# MultiRotor_0_1.net
KiCad netlist of a schematic drawn in Altium Designer
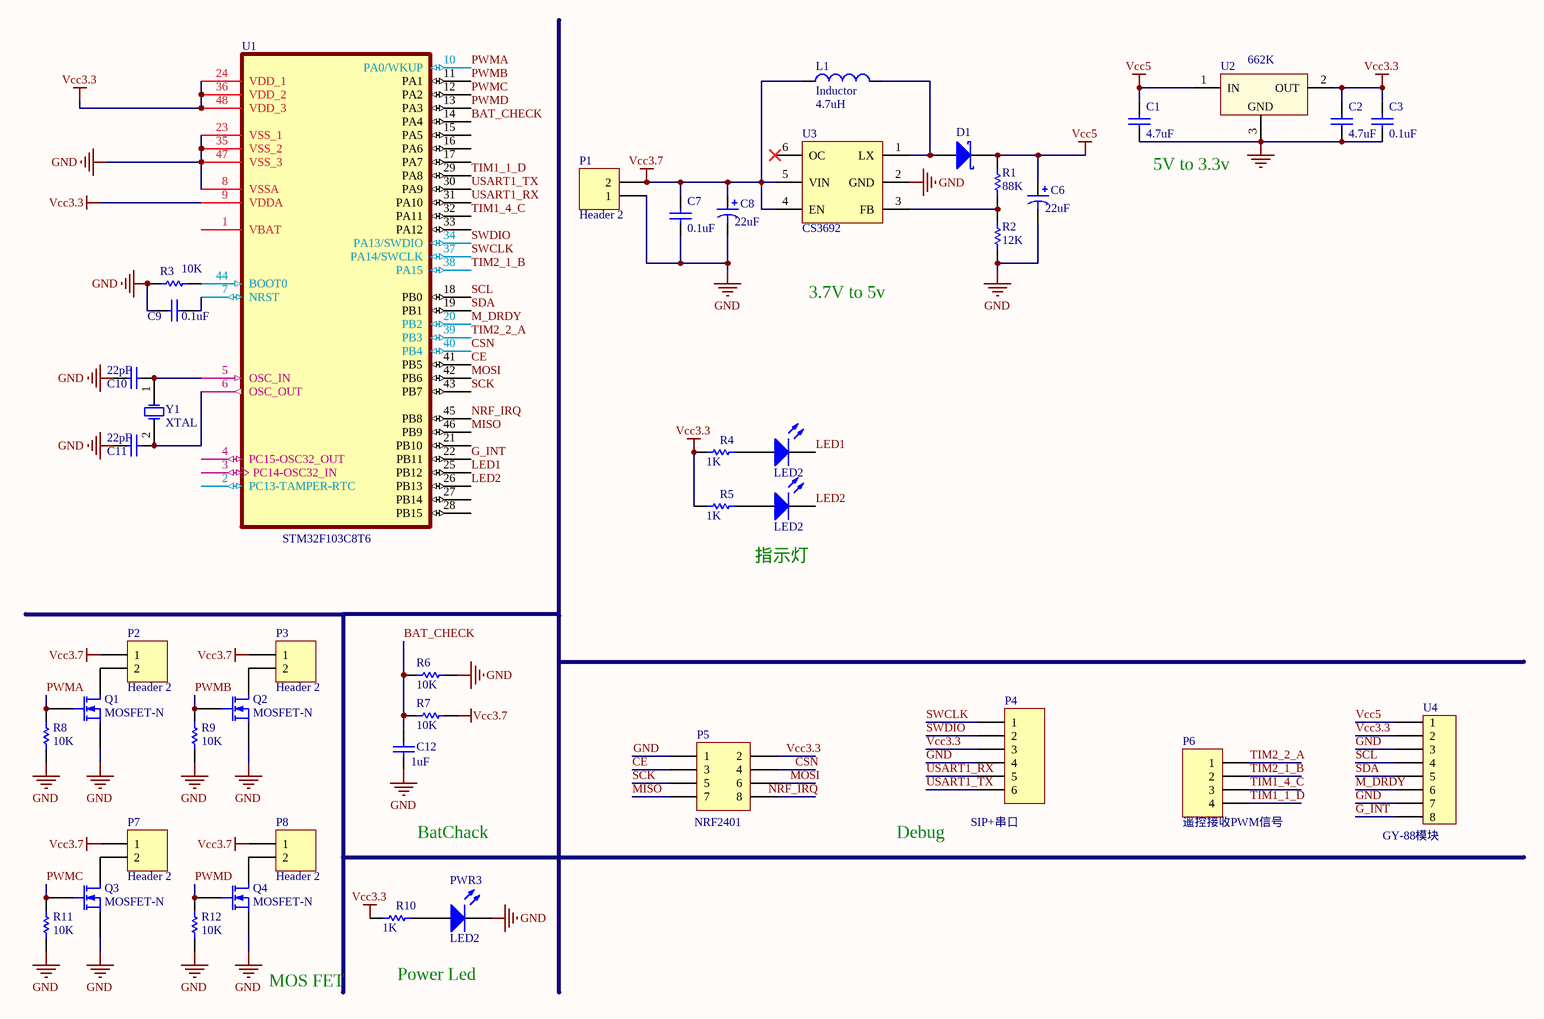
[diagram p0: MultiRotor_0.1.SchDoc]

(export (version "E")
  (design (tool "Eeschema 10.0.6"))
  (components
    (comp (ref "C1")
      (value "4.7uF")
      (footprint "CAP[1206]")
      (description "Capacitor")
      (fields (field (name "Comment") "Cap Pol1") (field (name "PUBLISHER") "Altium Limited"))
      (libsource (lib "Miscellaneous Devices") (part "Cap"))
    )
    (comp (ref "C2")
      (value "4.7uF")
      (footprint "CAP[1206]")
      (description "Capacitor")
      (fields (field (name "Comment") "Cap Pol1") (field (name "PUBLISHER") "Altium Limited"))
      (libsource (lib "Miscellaneous Devices") (part "Cap"))
    )
    (comp (ref "C3")
      (value "0.1uF")
      (footprint "CAP[0805]")
      (description "Capacitor")
      (fields (field (name "Comment") "Cap") (field (name "PUBLISHER") "Altium Limited"))
      (libsource (lib "Miscellaneous Devices") (part "Cap"))
    )
    (comp (ref "C6")
      (value "22uF")
      (footprint "CAP[1206]")
      (description "Polarized Capacitor (Radial)")
      (fields (field (name "Comment") "Cap") (field (name "PUBLISHER") "Altium Limited"))
      (libsource (lib "Miscellaneous Devices") (part "Cap Pol1"))
    )
    (comp (ref "C7")
      (value "0.1uF")
      (footprint "CAP[0805]")
      (description "Capacitor")
      (fields (field (name "Comment") "Cap") (field (name "PUBLISHER") "Altium Limited"))
      (libsource (lib "Miscellaneous Devices") (part "Cap"))
    )
    (comp (ref "C8")
      (value "22uF")
      (footprint "CAP[1206]")
      (description "Polarized Capacitor (Radial)")
      (fields (field (name "Comment") "Cap") (field (name "PUBLISHER") "Altium Limited"))
      (libsource (lib "Miscellaneous Devices") (part "Cap Pol1"))
    )
    (comp (ref "C9")
      (value "0.1uF")
      (footprint "CAP[0805]")
      (description "Capacitor")
      (fields (field (name "Comment") "Cap") (field (name "PUBLISHER") "Altium Limited"))
      (libsource (lib "Miscellaneous Devices") (part "Cap"))
    )
    (comp (ref "C10")
      (value "22pF")
      (footprint "CAP[0805]")
      (description "Capacitor")
      (fields (field (name "Comment") "Cap") (field (name "PUBLISHER") "Altium Limited"))
      (libsource (lib "Miscellaneous Devices") (part "Cap"))
    )
    (comp (ref "C11")
      (value "22pF")
      (footprint "CAP[0805]")
      (description "Capacitor")
      (fields (field (name "Comment") "Cap") (field (name "PUBLISHER") "Altium Limited"))
      (libsource (lib "Miscellaneous Devices") (part "Cap"))
    )
    (comp (ref "C12")
      (value "1uF")
      (footprint "CAP[0805]")
      (description "Capacitor")
      (fields (field (name "Comment") "Cap") (field (name "PUBLISHER") "Altium Limited"))
      (libsource (lib "Miscellaneous Devices") (part "Cap"))
    )
    (comp (ref "D1")
      (value "1n5819")
      (footprint "DO-214AC - Diode")
      (description "Diode_P6KE")
      (libsource (lib "BY") (part "Diode_P6KE"))
    )
    (comp (ref "L1")
      (value "Inductor")
      (footprint "Inductor_T10uH")
      (fields (field (name "ALTIUM_UNNAMED_1") "4.7uH"))
      (libsource (lib "BY") (part "Inductor"))
    )
    (comp (ref "P1")
      (value "Header 2")
      (footprint "H2.54-1X2")
      (description "Header, 2-Pin")
      (fields (field (name "PUBLISHER") "Altium Limited"))
      (libsource (lib "") (part "Header 2_1"))
    )
    (comp (ref "P2")
      (value "Header 2")
      (footprint "H2.54-1X2")
      (description "Header, 2-Pin")
      (fields (field (name "PUBLISHER") "Altium Limited"))
      (libsource (lib "Miscellaneous Connectors") (part "Header 2"))
    )
    (comp (ref "P3")
      (value "Header 2")
      (footprint "H2.54-1X2")
      (description "Header, 2-Pin")
      (fields (field (name "PUBLISHER") "Altium Limited"))
      (libsource (lib "Miscellaneous Connectors") (part "Header 2"))
    )
    (comp (ref "P4")
      (value "SIP+串口")
      (footprint "HDR1X6")
      (description "Header, 6-Pin")
      (fields (field (name "PUBLISHER") "Altium Limited"))
      (libsource (lib "Miscellaneous Connectors") (part "Header 6"))
    )
    (comp (ref "P5")
      (value "NRF2401")
      (footprint "NRF(2401)模块")
      (description "Header, 4-Pin, Dual row")
      (fields (field (name "PUBLISHER") "Altium Limited"))
      (libsource (lib "Miscellaneous Connectors") (part "Header 4X2"))
    )
    (comp (ref "P6")
      (value "遥控接收PWM信号")
      (footprint "H2.54-1X4")
      (description "Header, 4-Pin")
      (fields (field (name "PUBLISHER") "Altium Limited"))
      (libsource (lib "Miscellaneous Connectors") (part "Header 4"))
    )
    (comp (ref "P7")
      (value "Header 2")
      (footprint "H2.54-1X2")
      (description "Header, 2-Pin")
      (fields (field (name "PUBLISHER") "Altium Limited"))
      (libsource (lib "Miscellaneous Connectors") (part "Header 2"))
    )
    (comp (ref "P8")
      (value "Header 2")
      (footprint "H2.54-1X2")
      (description "Header, 2-Pin")
      (fields (field (name "PUBLISHER") "Altium Limited"))
      (libsource (lib "Miscellaneous Connectors") (part "Header 2"))
    )
    (comp (ref "PWR1")
      (value "LED2")
      (footprint "3.2X1.6X1.1")
      (description "Typical RED, GREEN, YELLOW, AMBER GaAs LED")
      (fields (field (name "PUBLISHER") "Altium Limited"))
      (libsource (lib "Miscellaneous Devices") (part "LED2"))
    )
    (comp (ref "PWR2")
      (value "LED2")
      (footprint "3.2X1.6X1.1")
      (description "Typical RED, GREEN, YELLOW, AMBER GaAs LED")
      (fields (field (name "PUBLISHER") "Altium Limited"))
      (libsource (lib "Miscellaneous Devices") (part "LED2"))
    )
    (comp (ref "PWR3")
      (value "LED2")
      (footprint "3.2X1.6X1.1")
      (description "Typical RED, GREEN, YELLOW, AMBER GaAs LED")
      (fields (field (name "PUBLISHER") "Altium Limited"))
      (libsource (lib "Miscellaneous Devices") (part "LED2"))
    )
    (comp (ref "Q1")
      (value "MOSFET-N")
      (footprint "SOT23")
      (description "N-Channel MOSFET")
      (fields (field (name "PUBLISHER") "Altium Limited"))
      (libsource (lib "Miscellaneous Devices") (part "MOSFET-N"))
    )
    (comp (ref "Q2")
      (value "MOSFET-N")
      (footprint "SOT23")
      (description "N-Channel MOSFET")
      (fields (field (name "PUBLISHER") "Altium Limited"))
      (libsource (lib "Miscellaneous Devices") (part "MOSFET-N"))
    )
    (comp (ref "Q3")
      (value "MOSFET-N")
      (footprint "SOT23")
      (description "N-Channel MOSFET")
      (fields (field (name "PUBLISHER") "Altium Limited"))
      (libsource (lib "Miscellaneous Devices") (part "MOSFET-N"))
    )
    (comp (ref "Q4")
      (value "MOSFET-N")
      (footprint "SOT23")
      (description "N-Channel MOSFET")
      (fields (field (name "PUBLISHER") "Altium Limited"))
      (libsource (lib "Miscellaneous Devices") (part "MOSFET-N"))
    )
    (comp (ref "R1")
      (value "88K")
      (footprint "RES[0805]")
      (description "Resistor")
      (fields (field (name "Comment") "Res1") (field (name "PUBLISHER") "Altium Limited"))
      (libsource (lib "Miscellaneous Devices") (part "Res1"))
    )
    (comp (ref "R2")
      (value "12K")
      (footprint "RES[0805]")
      (description "Resistor")
      (fields (field (name "Comment") "Res1") (field (name "PUBLISHER") "Altium Limited"))
      (libsource (lib "Miscellaneous Devices") (part "Res1"))
    )
    (comp (ref "R3")
      (value "10K")
      (footprint "RES[0805]")
      (description "Resistor")
      (fields (field (name "Comment") "Res1") (field (name "PUBLISHER") "Altium Limited"))
      (libsource (lib "Miscellaneous Devices") (part "Res1"))
    )
    (comp (ref "R4")
      (value "1K")
      (footprint "RES[0805]")
      (description "Resistor")
      (fields (field (name "Comment") "Res1") (field (name "PUBLISHER") "Altium Limited"))
      (libsource (lib "Miscellaneous Devices") (part "Res1"))
    )
    (comp (ref "R5")
      (value "1K")
      (footprint "RES[0805]")
      (description "Resistor")
      (fields (field (name "Comment") "Res1") (field (name "PUBLISHER") "Altium Limited"))
      (libsource (lib "Miscellaneous Devices") (part "Res1"))
    )
    (comp (ref "R6")
      (value "10K")
      (footprint "RES[0805]")
      (description "Resistor")
      (fields (field (name "Comment") "Res1") (field (name "PUBLISHER") "Altium Limited"))
      (libsource (lib "Miscellaneous Devices") (part "Res1"))
    )
    (comp (ref "R7")
      (value "10K")
      (footprint "RES[0805]")
      (description "Resistor")
      (fields (field (name "Comment") "Res1") (field (name "PUBLISHER") "Altium Limited"))
      (libsource (lib "Miscellaneous Devices") (part "Res1"))
    )
    (comp (ref "R8")
      (value "10K")
      (footprint "RES[0805]")
      (description "Resistor")
      (fields (field (name "Comment") "Res1") (field (name "PUBLISHER") "Altium Limited"))
      (libsource (lib "Miscellaneous Devices") (part "Res1"))
    )
    (comp (ref "R9")
      (value "10K")
      (footprint "RES[0805]")
      (description "Resistor")
      (fields (field (name "Comment") "Res1") (field (name "PUBLISHER") "Altium Limited"))
      (libsource (lib "Miscellaneous Devices") (part "Res1"))
    )
    (comp (ref "R10")
      (value "1K")
      (footprint "RES[0805]")
      (description "Resistor")
      (fields (field (name "Comment") "Res1") (field (name "PUBLISHER") "Altium Limited"))
      (libsource (lib "Miscellaneous Devices") (part "Res1"))
    )
    (comp (ref "R11")
      (value "10K")
      (footprint "RES[0805]")
      (description "Resistor")
      (fields (field (name "Comment") "Res1") (field (name "PUBLISHER") "Altium Limited"))
      (libsource (lib "Miscellaneous Devices") (part "Res1"))
    )
    (comp (ref "R12")
      (value "10K")
      (footprint "RES[0805]")
      (description "Resistor")
      (fields (field (name "Comment") "Res1") (field (name "PUBLISHER") "Altium Limited"))
      (libsource (lib "Miscellaneous Devices") (part "Res1"))
    )
    (comp (ref "U1")
      (value "STM32F103C8T6")
      (footprint "LQFP-48")
      (description "STM32 ARM-based 32-bit MCU with 64 Kbytes Flash, 48-pin LQFP, Industrial Temperature")
      (fields (field (name "PUBLISHER") "*"))
      (libsource (lib "STM32F103C8T6") (part "STM32F103C8T6"))
    )
    (comp (ref "U2") (value "662K") (footprint "SOT23") (libsource (lib "WB") (part "AMS1117-3.3")))
    (comp (ref "U3")
      (value "CS3692")
      (footprint "SOT23-6")
      (description "Generic Phase Locked Loop")
      (fields (field (name "PUBLISHER") "Altium Limited"))
      (libsource (lib "MultiRotor") (part "CS3692"))
    )
    (comp (ref "U4") (value "GY-88模块") (footprint "MPU-6050") (libsource (lib "FAST") (part "MPU-6050模块")))
    (comp (ref "Y1")
      (value "XTAL")
      (footprint "XTAL")
      (description "Crystal Oscillator")
      (fields (field (name "PUBLISHER") "Altium Limited"))
      (libsource (lib "Miscellaneous Devices") (part "XTAL"))
    )
  )
  (nets
    (net (code "1") (name "/BAT_CHECK") (class "Default")
      (node (ref "C12") (pin "2") (pinfunction "2_2") (pintype "passive"))
      (node (ref "R6") (pin "2") (pinfunction "2_2") (pintype "passive"))
      (node (ref "R7") (pin "2") (pinfunction "2_2") (pintype "passive"))
      (node (ref "U1") (pin "14") (pinfunction "PA4_14") (pintype "bidirectional"))
    )
    (net (code "2") (name "/CE") (class "Default")
      (node (ref "P5") (pin "3") (pinfunction "3_3") (pintype "passive"))
      (node (ref "U1") (pin "41") (pinfunction "PB5_41") (pintype "bidirectional"))
    )
    (net (code "3") (name "/CSN") (class "Default")
      (node (ref "P5") (pin "4") (pinfunction "4_4") (pintype "passive"))
      (node (ref "U1") (pin "40") (pinfunction "PB4_40") (pintype "bidirectional"))
    )
    (net (code "4") (name "/G_INT") (class "Default")
      (node (ref "U1") (pin "22") (pinfunction "PB11_22") (pintype "bidirectional"))
      (node (ref "U4") (pin "8") (pinfunction "8_8") (pintype "passive"))
    )
    (net (code "5") (name "/LED1") (class "Default")
      (node (ref "PWR1") (pin "2") (pinfunction "K_2") (pintype "passive"))
      (node (ref "U1") (pin "25") (pinfunction "PB12_25") (pintype "bidirectional"))
    )
    (net (code "6") (name "/LED2") (class "Default")
      (node (ref "PWR2") (pin "2") (pinfunction "K_2") (pintype "passive"))
      (node (ref "U1") (pin "26") (pinfunction "PB13_26") (pintype "bidirectional"))
    )
    (net (code "7") (name "/MISO") (class "Default")
      (node (ref "P5") (pin "7") (pinfunction "7_7") (pintype "passive"))
      (node (ref "U1") (pin "46") (pinfunction "PB9_46") (pintype "bidirectional"))
    )
    (net (code "8") (name "/MOSI") (class "Default")
      (node (ref "P5") (pin "6") (pinfunction "6_6") (pintype "passive"))
      (node (ref "U1") (pin "42") (pinfunction "PB6_42") (pintype "bidirectional"))
    )
    (net (code "9") (name "/M_DRDY") (class "Default")
      (node (ref "U1") (pin "20") (pinfunction "PB2_20") (pintype "bidirectional"))
      (node (ref "U4") (pin "6") (pinfunction "6_6") (pintype "passive"))
    )
    (net (code "10") (name "/NRF_IRQ") (class "Default")
      (node (ref "U1") (pin "45") (pinfunction "PB8_45") (pintype "bidirectional"))
    )
    (net (code "11") (name "/PWMA") (class "Default")
      (node (ref "Q1") (pin "2") (pinfunction "G_2") (pintype "passive"))
      (node (ref "R8") (pin "2") (pinfunction "2_2") (pintype "passive"))
      (node (ref "U1") (pin "10") (pinfunction "PA0/WKUP_10") (pintype "bidirectional"))
    )
    (net (code "12") (name "/PWMB") (class "Default")
      (node (ref "Q2") (pin "2") (pinfunction "G_2") (pintype "passive"))
      (node (ref "R9") (pin "2") (pinfunction "2_2") (pintype "passive"))
      (node (ref "U1") (pin "11") (pinfunction "PA1_11") (pintype "bidirectional"))
    )
    (net (code "13") (name "/PWMC") (class "Default")
      (node (ref "Q3") (pin "2") (pinfunction "G_2") (pintype "passive"))
      (node (ref "R11") (pin "2") (pinfunction "2_2") (pintype "passive"))
      (node (ref "U1") (pin "12") (pinfunction "PA2_12") (pintype "bidirectional"))
    )
    (net (code "14") (name "/PWMD") (class "Default")
      (node (ref "Q4") (pin "2") (pinfunction "G_2") (pintype "passive"))
      (node (ref "R12") (pin "2") (pinfunction "2_2") (pintype "passive"))
      (node (ref "U1") (pin "13") (pinfunction "PA3_13") (pintype "bidirectional"))
    )
    (net (code "15") (name "/SCK") (class "Default")
      (node (ref "P5") (pin "5") (pinfunction "5_5") (pintype "passive"))
      (node (ref "U1") (pin "43") (pinfunction "PB7_43") (pintype "bidirectional"))
    )
    (net (code "16") (name "/SCL") (class "Default")
      (node (ref "U1") (pin "18") (pinfunction "PB0_18") (pintype "bidirectional"))
      (node (ref "U4") (pin "4") (pinfunction "4_4") (pintype "passive"))
    )
    (net (code "17") (name "/SDA") (class "Default")
      (node (ref "U1") (pin "19") (pinfunction "PB1_19") (pintype "bidirectional"))
      (node (ref "U4") (pin "5") (pinfunction "5_5") (pintype "passive"))
    )
    (net (code "18") (name "/SWCLK") (class "Default")
      (node (ref "P4") (pin "1") (pinfunction "1_1") (pintype "passive"))
      (node (ref "U1") (pin "37") (pinfunction "PA14/SWCLK_37") (pintype "bidirectional"))
    )
    (net (code "19") (name "/SWDIO") (class "Default")
      (node (ref "P4") (pin "2") (pinfunction "2_2") (pintype "passive"))
      (node (ref "U1") (pin "34") (pinfunction "PA13/SWDIO_34") (pintype "bidirectional"))
    )
    (net (code "20") (name "/TIM1_1_D") (class "Default")
      (node (ref "P6") (pin "4") (pinfunction "4_4") (pintype "passive"))
      (node (ref "U1") (pin "29") (pinfunction "PA8_29") (pintype "bidirectional"))
    )
    (net (code "21") (name "/TIM1_4_C") (class "Default")
      (node (ref "P6") (pin "3") (pinfunction "3_3") (pintype "passive"))
      (node (ref "U1") (pin "32") (pinfunction "PA11_32") (pintype "bidirectional"))
    )
    (net (code "22") (name "/TIM2_1_B") (class "Default")
      (node (ref "P6") (pin "2") (pinfunction "2_2") (pintype "passive"))
      (node (ref "U1") (pin "38") (pinfunction "PA15_38") (pintype "bidirectional"))
    )
    (net (code "23") (name "/TIM2_2_A") (class "Default")
      (node (ref "P6") (pin "1") (pinfunction "1_1") (pintype "passive"))
      (node (ref "U1") (pin "39") (pinfunction "PB3_39") (pintype "bidirectional"))
    )
    (net (code "24") (name "/USART1_RX") (class "Default")
      (node (ref "P4") (pin "5") (pinfunction "5_5") (pintype "passive"))
      (node (ref "U1") (pin "31") (pinfunction "PA10_31") (pintype "bidirectional"))
    )
    (net (code "25") (name "/USART1_TX") (class "Default")
      (node (ref "P4") (pin "6") (pinfunction "6_6") (pintype "passive"))
      (node (ref "U1") (pin "30") (pinfunction "PA9_30") (pintype "bidirectional"))
    )
    (net (code "26") (name "GND") (class "Default")
      (node (ref "C1") (pin "1") (pinfunction "1_1") (pintype "passive"))
      (node (ref "C10") (pin "2") (pinfunction "2_2") (pintype "passive"))
      (node (ref "C11") (pin "2") (pinfunction "2_2") (pintype "passive"))
      (node (ref "C12") (pin "1") (pinfunction "1_1") (pintype "passive"))
      (node (ref "C2") (pin "1") (pinfunction "1_1") (pintype "passive"))
      (node (ref "C3") (pin "1") (pinfunction "1_1") (pintype "passive"))
      (node (ref "C6") (pin "2") (pinfunction "2_2") (pintype "passive"))
      (node (ref "C7") (pin "1") (pinfunction "1_1") (pintype "passive"))
      (node (ref "C8") (pin "2") (pinfunction "2_2") (pintype "passive"))
      (node (ref "C9") (pin "2") (pinfunction "2_2") (pintype "passive"))
      (node (ref "P1") (pin "1") (pinfunction "1_1") (pintype "passive"))
      (node (ref "P4") (pin "4") (pinfunction "4_4") (pintype "passive"))
      (node (ref "P5") (pin "1") (pinfunction "1_1") (pintype "passive"))
      (node (ref "PWR3") (pin "2") (pinfunction "K_2") (pintype "passive"))
      (node (ref "Q1") (pin "3") (pinfunction "S_3") (pintype "passive"))
      (node (ref "Q2") (pin "3") (pinfunction "S_3") (pintype "passive"))
      (node (ref "Q3") (pin "3") (pinfunction "S_3") (pintype "passive"))
      (node (ref "Q4") (pin "3") (pinfunction "S_3") (pintype "passive"))
      (node (ref "R11") (pin "1") (pinfunction "1_1") (pintype "passive"))
      (node (ref "R12") (pin "1") (pinfunction "1_1") (pintype "passive"))
      (node (ref "R2") (pin "2") (pinfunction "2_2") (pintype "passive"))
      (node (ref "R3") (pin "2") (pinfunction "2_2") (pintype "passive"))
      (node (ref "R6") (pin "1") (pinfunction "1_1") (pintype "passive"))
      (node (ref "R8") (pin "1") (pinfunction "1_1") (pintype "passive"))
      (node (ref "R9") (pin "1") (pinfunction "1_1") (pintype "passive"))
      (node (ref "U1") (pin "23") (pinfunction "VSS_1_23") (pintype "power_in"))
      (node (ref "U1") (pin "35") (pinfunction "VSS_2_35") (pintype "power_in"))
      (node (ref "U1") (pin "47") (pinfunction "VSS_3_47") (pintype "power_in"))
      (node (ref "U1") (pin "8") (pinfunction "VSSA_8") (pintype "power_in"))
      (node (ref "U2") (pin "3") (pinfunction "GND_3") (pintype "passive"))
      (node (ref "U3") (pin "2") (pinfunction "GND_2") (pintype "passive"))
      (node (ref "U4") (pin "3") (pinfunction "3_3") (pintype "passive"))
      (node (ref "U4") (pin "7") (pinfunction "7_7") (pintype "passive"))
    )
    (net (code "27") (name "Net-(D1-A)") (class "Default")
      (node (ref "D1") (pin "1") (pinfunction "A_1") (pintype "passive"))
      (node (ref "L1") (pin "2") (pinfunction "2_2") (pintype "passive"))
      (node (ref "U3") (pin "1") (pinfunction "LX_1") (pintype "passive"))
    )
    (net (code "28") (name "Net-(PWR1-A)") (class "Default")
      (node (ref "PWR1") (pin "1") (pinfunction "A_1") (pintype "passive"))
      (node (ref "R4") (pin "1") (pinfunction "1_1") (pintype "passive"))
    )
    (net (code "29") (name "Net-(PWR2-A)") (class "Default")
      (node (ref "PWR2") (pin "1") (pinfunction "A_1") (pintype "passive"))
      (node (ref "R5") (pin "1") (pinfunction "1_1") (pintype "passive"))
    )
    (net (code "30") (name "Net-(PWR3-A)") (class "Default")
      (node (ref "PWR3") (pin "1") (pinfunction "A_1") (pintype "passive"))
      (node (ref "R10") (pin "1") (pinfunction "1_1") (pintype "passive"))
    )
    (net (code "31") (name "Net-(Q1-D)") (class "Default")
      (node (ref "P2") (pin "2") (pinfunction "2_2") (pintype "passive"))
      (node (ref "Q1") (pin "1") (pinfunction "D_1") (pintype "passive"))
    )
    (net (code "32") (name "Net-(Q2-D)") (class "Default")
      (node (ref "P3") (pin "2") (pinfunction "2_2") (pintype "passive"))
      (node (ref "Q2") (pin "1") (pinfunction "D_1") (pintype "passive"))
    )
    (net (code "33") (name "Net-(Q3-D)") (class "Default")
      (node (ref "P7") (pin "2") (pinfunction "2_2") (pintype "passive"))
      (node (ref "Q3") (pin "1") (pinfunction "D_1") (pintype "passive"))
    )
    (net (code "34") (name "Net-(Q4-D)") (class "Default")
      (node (ref "P8") (pin "2") (pinfunction "2_2") (pintype "passive"))
      (node (ref "Q4") (pin "1") (pinfunction "D_1") (pintype "passive"))
    )
    (net (code "35") (name "Net-(U1-BOOT0)") (class "Default")
      (node (ref "R3") (pin "1") (pinfunction "1_1") (pintype "passive"))
      (node (ref "U1") (pin "44") (pinfunction "BOOT0_44") (pintype "input"))
    )
    (net (code "36") (name "Net-(U1-NRST)") (class "Default")
      (node (ref "C9") (pin "1") (pinfunction "1_1") (pintype "passive"))
      (node (ref "U1") (pin "7") (pinfunction "NRST_7") (pintype "bidirectional"))
    )
    (net (code "37") (name "Net-(U1-OSC_IN)") (class "Default")
      (node (ref "C10") (pin "1") (pinfunction "1_1") (pintype "passive"))
      (node (ref "U1") (pin "5") (pinfunction "OSC_IN_5") (pintype "input"))
      (node (ref "Y1") (pin "1") (pinfunction "OSC1_1") (pintype "passive"))
    )
    (net (code "38") (name "Net-(U1-OSC_OUT)") (class "Default")
      (node (ref "C11") (pin "1") (pinfunction "1_1") (pintype "passive"))
      (node (ref "U1") (pin "6") (pinfunction "OSC_OUT_6") (pintype "output"))
      (node (ref "Y1") (pin "2") (pinfunction "OSC2_2") (pintype "passive"))
    )
    (net (code "39") (name "Net-(U3-FB)") (class "Default")
      (node (ref "R1") (pin "2") (pinfunction "2_2") (pintype "passive"))
      (node (ref "R2") (pin "1") (pinfunction "1_1") (pintype "passive"))
      (node (ref "U3") (pin "3") (pinfunction "FB_3") (pintype "passive"))
    )
    (net (code "40") (name "Vcc3.3") (class "Default")
      (node (ref "C2") (pin "2") (pinfunction "2_2") (pintype "passive"))
      (node (ref "C3") (pin "2") (pinfunction "2_2") (pintype "passive"))
      (node (ref "P4") (pin "3") (pinfunction "3_3") (pintype "passive"))
      (node (ref "P5") (pin "2") (pinfunction "2_2") (pintype "passive"))
      (node (ref "R10") (pin "2") (pinfunction "2_2") (pintype "passive"))
      (node (ref "R4") (pin "2") (pinfunction "2_2") (pintype "passive"))
      (node (ref "R5") (pin "2") (pinfunction "2_2") (pintype "passive"))
      (node (ref "U1") (pin "24") (pinfunction "VDD_1_24") (pintype "power_in"))
      (node (ref "U1") (pin "36") (pinfunction "VDD_2_36") (pintype "power_in"))
      (node (ref "U1") (pin "48") (pinfunction "VDD_3_48") (pintype "power_in"))
      (node (ref "U1") (pin "9") (pinfunction "VDDA_9") (pintype "power_in"))
      (node (ref "U2") (pin "2") (pinfunction "OUT_2") (pintype "passive"))
      (node (ref "U4") (pin "2") (pinfunction "2_2") (pintype "passive"))
    )
    (net (code "41") (name "Vcc3.7") (class "Default")
      (node (ref "C7") (pin "2") (pinfunction "2_2") (pintype "passive"))
      (node (ref "C8") (pin "1") (pinfunction "1_1") (pintype "passive"))
      (node (ref "L1") (pin "1") (pinfunction "1_1") (pintype "passive"))
      (node (ref "P1") (pin "2") (pinfunction "2_2") (pintype "passive"))
      (node (ref "P2") (pin "1") (pinfunction "1_1") (pintype "passive"))
      (node (ref "P3") (pin "1") (pinfunction "1_1") (pintype "passive"))
      (node (ref "P7") (pin "1") (pinfunction "1_1") (pintype "passive"))
      (node (ref "P8") (pin "1") (pinfunction "1_1") (pintype "passive"))
      (node (ref "R7") (pin "1") (pinfunction "1_1") (pintype "passive"))
      (node (ref "U3") (pin "4") (pinfunction "EN_4") (pintype "passive"))
      (node (ref "U3") (pin "5") (pinfunction "VIN_5") (pintype "passive"))
    )
    (net (code "42") (name "Vcc5") (class "Default")
      (node (ref "C1") (pin "2") (pinfunction "2_2") (pintype "passive"))
      (node (ref "C6") (pin "1") (pinfunction "1_1") (pintype "passive"))
      (node (ref "D1") (pin "2") (pinfunction "K_2") (pintype "passive"))
      (node (ref "R1") (pin "1") (pinfunction "1_1") (pintype "passive"))
      (node (ref "U2") (pin "1") (pinfunction "IN_1") (pintype "passive"))
      (node (ref "U4") (pin "1") (pinfunction "1_1") (pintype "passive"))
    )
    (net (code "43") (name "unconnected-(P5-Pad8)") (class "Default")
      (node (ref "P5") (pin "8") (pinfunction "8_8") (pintype "passive"))
    )
    (net (code "44") (name "unconnected-(U1-PA5-Pad15)") (class "Default")
      (node (ref "U1") (pin "15") (pinfunction "PA5_15") (pintype "bidirectional"))
    )
    (net (code "45") (name "unconnected-(U1-PA6-Pad16)") (class "Default")
      (node (ref "U1") (pin "16") (pinfunction "PA6_16") (pintype "bidirectional"))
    )
    (net (code "46") (name "unconnected-(U1-PA7-Pad17)") (class "Default")
      (node (ref "U1") (pin "17") (pinfunction "PA7_17") (pintype "bidirectional"))
    )
    (net (code "47") (name "unconnected-(U1-PA12-Pad33)") (class "Default")
      (node (ref "U1") (pin "33") (pinfunction "PA12_33") (pintype "bidirectional"))
    )
    (net (code "48") (name "unconnected-(U1-PB10-Pad21)") (class "Default")
      (node (ref "U1") (pin "21") (pinfunction "PB10_21") (pintype "bidirectional"))
    )
    (net (code "49") (name "unconnected-(U1-PB14-Pad27)") (class "Default")
      (node (ref "U1") (pin "27") (pinfunction "PB14_27") (pintype "bidirectional"))
    )
    (net (code "50") (name "unconnected-(U1-PB15-Pad28)") (class "Default")
      (node (ref "U1") (pin "28") (pinfunction "PB15_28") (pintype "bidirectional"))
    )
    (net (code "51") (name "unconnected-(U1-PC13-TAMPER-RTC-Pad2)") (class "Default")
      (node (ref "U1") (pin "2") (pinfunction "PC13-TAMPER-RTC_2") (pintype "bidirectional"))
    )
    (net (code "52") (name "unconnected-(U1-PC14-OSC32_IN-Pad3)") (class "Default")
      (node (ref "U1") (pin "3") (pinfunction "PC14-OSC32_IN_3") (pintype "bidirectional"))
    )
    (net (code "53") (name "unconnected-(U1-PC15-OSC32_OUT-Pad4)") (class "Default")
      (node (ref "U1") (pin "4") (pinfunction "PC15-OSC32_OUT_4") (pintype "bidirectional"))
    )
    (net (code "54") (name "unconnected-(U1-VBAT-Pad1)") (class "Default")
      (node (ref "U1") (pin "1") (pinfunction "VBAT_1") (pintype "power_in"))
    )
    (net (code "55") (name "unconnected-(U3-OC-Pad6)") (class "Default")
      (node (ref "U3") (pin "6") (pinfunction "OC_6") (pintype "passive+no_connect"))
    )
  )
)
